# ws2812b-tree-test.net
KiCad netlist of a schematic drawn in EAGLE
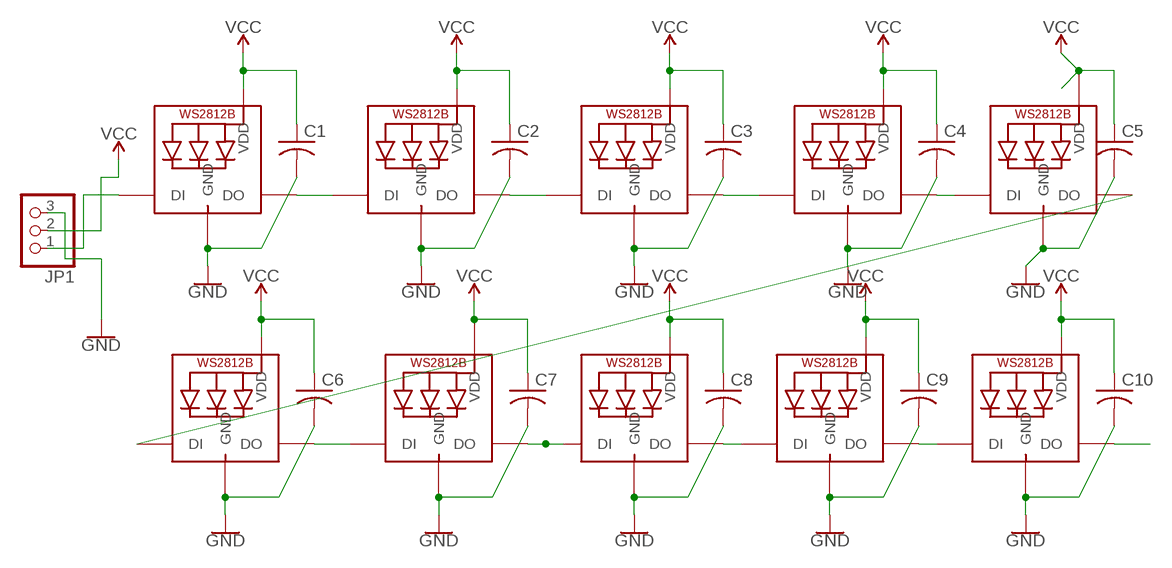
[diagram p0: schematic, sheet 1]

(export (version "E")
  (design (tool "Eeschema 10.0.6"))
  (components
    (comp (ref "C1")
      (value "C-USC3216")
      (footprint "eagle-import:C3216")
      (libsource (lib "eagle-import") (part "C-USC3216"))
    )
    (comp (ref "C2")
      (value "C-USC3216")
      (footprint "eagle-import:C3216")
      (libsource (lib "eagle-import") (part "C-USC3216"))
    )
    (comp (ref "C3")
      (value "C-USC3216")
      (footprint "eagle-import:C3216")
      (libsource (lib "eagle-import") (part "C-USC3216"))
    )
    (comp (ref "C4")
      (value "C-USC3216")
      (footprint "eagle-import:C3216")
      (libsource (lib "eagle-import") (part "C-USC3216"))
    )
    (comp (ref "C5")
      (value "C-USC3216")
      (footprint "eagle-import:C3216")
      (libsource (lib "eagle-import") (part "C-USC3216"))
    )
    (comp (ref "C6")
      (value "C-USC3216")
      (footprint "eagle-import:C3216")
      (libsource (lib "eagle-import") (part "C-USC3216"))
    )
    (comp (ref "C7")
      (value "C-USC3216")
      (footprint "eagle-import:C3216")
      (libsource (lib "eagle-import") (part "C-USC3216"))
    )
    (comp (ref "C8")
      (value "C-USC3216")
      (footprint "eagle-import:C3216")
      (libsource (lib "eagle-import") (part "C-USC3216"))
    )
    (comp (ref "C9")
      (value "C-USC3216")
      (footprint "eagle-import:C3216")
      (libsource (lib "eagle-import") (part "C-USC3216"))
    )
    (comp (ref "C10")
      (value "C-USC3216")
      (footprint "eagle-import:C3216")
      (libsource (lib "eagle-import") (part "C-USC3216"))
    )
    (comp (ref "JP1")
      (value "PINHD-1X3")
      (footprint "eagle-import:1X03")
      (libsource (lib "eagle-import") (part "PINHD-1X3"))
    )
    (comp (ref "LED1")
      (value "WS2812B5050")
      (footprint "eagle-import:WS2812B")
      (libsource (lib "eagle-import") (part "WS2812B5050"))
    )
    (comp (ref "LED2")
      (value "WS2812B5050")
      (footprint "eagle-import:WS2812B")
      (libsource (lib "eagle-import") (part "WS2812B5050"))
    )
    (comp (ref "LED3")
      (value "WS2812B5050")
      (footprint "eagle-import:WS2812B")
      (libsource (lib "eagle-import") (part "WS2812B5050"))
    )
    (comp (ref "LED4")
      (value "WS2812B5050")
      (footprint "eagle-import:WS2812B")
      (libsource (lib "eagle-import") (part "WS2812B5050"))
    )
    (comp (ref "LED5")
      (value "WS2812B5050")
      (footprint "eagle-import:WS2812B")
      (libsource (lib "eagle-import") (part "WS2812B5050"))
    )
    (comp (ref "LED6")
      (value "WS2812B5050")
      (footprint "eagle-import:WS2812B")
      (libsource (lib "eagle-import") (part "WS2812B5050"))
    )
    (comp (ref "LED7")
      (value "WS2812B5050")
      (footprint "eagle-import:WS2812B")
      (libsource (lib "eagle-import") (part "WS2812B5050"))
    )
    (comp (ref "LED8")
      (value "WS2812B5050")
      (footprint "eagle-import:WS2812B")
      (libsource (lib "eagle-import") (part "WS2812B5050"))
    )
    (comp (ref "LED9")
      (value "WS2812B5050")
      (footprint "eagle-import:WS2812B")
      (libsource (lib "eagle-import") (part "WS2812B5050"))
    )
    (comp (ref "LED10")
      (value "WS2812B5050")
      (footprint "eagle-import:WS2812B")
      (libsource (lib "eagle-import") (part "WS2812B5050"))
    )
  )
  (nets
    (net (code "1") (name "GND") (class "Default")
      (node (ref "C1") (pin "2") (pinfunction "2_2") (pintype "passive"))
      (node (ref "C10") (pin "2") (pinfunction "2_2") (pintype "passive"))
      (node (ref "C2") (pin "2") (pinfunction "2_2") (pintype "passive"))
      (node (ref "C3") (pin "2") (pinfunction "2_2") (pintype "passive"))
      (node (ref "C4") (pin "2") (pinfunction "2_2") (pintype "passive"))
      (node (ref "C5") (pin "2") (pinfunction "2_2") (pintype "passive"))
      (node (ref "C6") (pin "2") (pinfunction "2_2") (pintype "passive"))
      (node (ref "C7") (pin "2") (pinfunction "2_2") (pintype "passive"))
      (node (ref "C8") (pin "2") (pinfunction "2_2") (pintype "passive"))
      (node (ref "C9") (pin "2") (pinfunction "2_2") (pintype "passive"))
      (node (ref "JP1") (pin "3") (pinfunction "3_3") (pintype "passive"))
      (node (ref "LED1") (pin "3-GND") (pinfunction "GND_3-GND") (pintype "power_in"))
      (node (ref "LED10") (pin "3-GND") (pinfunction "GND_3-GND") (pintype "power_in"))
      (node (ref "LED2") (pin "3-GND") (pinfunction "GND_3-GND") (pintype "power_in"))
      (node (ref "LED3") (pin "3-GND") (pinfunction "GND_3-GND") (pintype "power_in"))
      (node (ref "LED4") (pin "3-GND") (pinfunction "GND_3-GND") (pintype "power_in"))
      (node (ref "LED5") (pin "3-GND") (pinfunction "GND_3-GND") (pintype "power_in"))
      (node (ref "LED6") (pin "3-GND") (pinfunction "GND_3-GND") (pintype "power_in"))
      (node (ref "LED7") (pin "3-GND") (pinfunction "GND_3-GND") (pintype "power_in"))
      (node (ref "LED8") (pin "3-GND") (pinfunction "GND_3-GND") (pintype "power_in"))
      (node (ref "LED9") (pin "3-GND") (pinfunction "GND_3-GND") (pintype "power_in"))
    )
    (net (code "2") (name "Net-(LED1-DI)") (class "Default")
      (node (ref "JP1") (pin "1") (pinfunction "1_1") (pintype "passive"))
      (node (ref "LED1") (pin "4-DIN") (pinfunction "DI_4-DIN") (pintype "input"))
    )
    (net (code "3") (name "Net-(LED1-DO)") (class "Default")
      (node (ref "LED1") (pin "2-DOUT") (pinfunction "DO_2-DOUT") (pintype "output"))
      (node (ref "LED2") (pin "4-DIN") (pinfunction "DI_4-DIN") (pintype "input"))
    )
    (net (code "4") (name "Net-(LED2-DO)") (class "Default")
      (node (ref "LED2") (pin "2-DOUT") (pinfunction "DO_2-DOUT") (pintype "output"))
      (node (ref "LED3") (pin "4-DIN") (pinfunction "DI_4-DIN") (pintype "input"))
    )
    (net (code "5") (name "Net-(LED3-DO)") (class "Default")
      (node (ref "LED3") (pin "2-DOUT") (pinfunction "DO_2-DOUT") (pintype "output"))
      (node (ref "LED4") (pin "4-DIN") (pinfunction "DI_4-DIN") (pintype "input"))
    )
    (net (code "6") (name "Net-(LED4-DO)") (class "Default")
      (node (ref "LED4") (pin "2-DOUT") (pinfunction "DO_2-DOUT") (pintype "output"))
      (node (ref "LED5") (pin "4-DIN") (pinfunction "DI_4-DIN") (pintype "input"))
    )
    (net (code "7") (name "Net-(LED5-DO)") (class "Default")
      (node (ref "LED5") (pin "2-DOUT") (pinfunction "DO_2-DOUT") (pintype "output"))
      (node (ref "LED6") (pin "4-DIN") (pinfunction "DI_4-DIN") (pintype "input"))
    )
    (net (code "8") (name "Net-(LED6-DO)") (class "Default")
      (node (ref "LED6") (pin "2-DOUT") (pinfunction "DO_2-DOUT") (pintype "output"))
      (node (ref "LED7") (pin "4-DIN") (pinfunction "DI_4-DIN") (pintype "input"))
    )
    (net (code "9") (name "Net-(LED7-DO)") (class "Default")
      (node (ref "LED7") (pin "2-DOUT") (pinfunction "DO_2-DOUT") (pintype "output"))
      (node (ref "LED8") (pin "4-DIN") (pinfunction "DI_4-DIN") (pintype "input"))
    )
    (net (code "10") (name "Net-(LED8-DO)") (class "Default")
      (node (ref "LED8") (pin "2-DOUT") (pinfunction "DO_2-DOUT") (pintype "output"))
      (node (ref "LED9") (pin "4-DIN") (pinfunction "DI_4-DIN") (pintype "input"))
    )
    (net (code "11") (name "Net-(LED10-DI)") (class "Default")
      (node (ref "LED10") (pin "4-DIN") (pinfunction "DI_4-DIN") (pintype "input"))
      (node (ref "LED9") (pin "2-DOUT") (pinfunction "DO_2-DOUT") (pintype "output"))
    )
    (net (code "12") (name "VCC") (class "Default")
      (node (ref "C1") (pin "1") (pinfunction "1_1") (pintype "passive"))
      (node (ref "C10") (pin "1") (pinfunction "1_1") (pintype "passive"))
      (node (ref "C2") (pin "1") (pinfunction "1_1") (pintype "passive"))
      (node (ref "C3") (pin "1") (pinfunction "1_1") (pintype "passive"))
      (node (ref "C4") (pin "1") (pinfunction "1_1") (pintype "passive"))
      (node (ref "C5") (pin "1") (pinfunction "1_1") (pintype "passive"))
      (node (ref "C6") (pin "1") (pinfunction "1_1") (pintype "passive"))
      (node (ref "C7") (pin "1") (pinfunction "1_1") (pintype "passive"))
      (node (ref "C8") (pin "1") (pinfunction "1_1") (pintype "passive"))
      (node (ref "C9") (pin "1") (pinfunction "1_1") (pintype "passive"))
      (node (ref "JP1") (pin "2") (pinfunction "2_2") (pintype "passive"))
      (node (ref "LED1") (pin "1-VDD") (pinfunction "VDD_1-VDD") (pintype "power_in"))
      (node (ref "LED10") (pin "1-VDD") (pinfunction "VDD_1-VDD") (pintype "power_in"))
      (node (ref "LED2") (pin "1-VDD") (pinfunction "VDD_1-VDD") (pintype "power_in"))
      (node (ref "LED3") (pin "1-VDD") (pinfunction "VDD_1-VDD") (pintype "power_in"))
      (node (ref "LED4") (pin "1-VDD") (pinfunction "VDD_1-VDD") (pintype "power_in"))
      (node (ref "LED5") (pin "1-VDD") (pinfunction "VDD_1-VDD") (pintype "power_in"))
      (node (ref "LED6") (pin "1-VDD") (pinfunction "VDD_1-VDD") (pintype "power_in"))
      (node (ref "LED7") (pin "1-VDD") (pinfunction "VDD_1-VDD") (pintype "power_in"))
      (node (ref "LED8") (pin "1-VDD") (pinfunction "VDD_1-VDD") (pintype "power_in"))
      (node (ref "LED9") (pin "1-VDD") (pinfunction "VDD_1-VDD") (pintype "power_in"))
    )
    (net (code "13") (name "unconnected-(LED10-DO-Pad2-DOUT)") (class "Default")
      (node (ref "LED10") (pin "2-DOUT") (pinfunction "DO_2-DOUT") (pintype "output"))
    )
  )
)
